# wifiserial.net
KiCad netlist of a schematic drawn in EAGLE
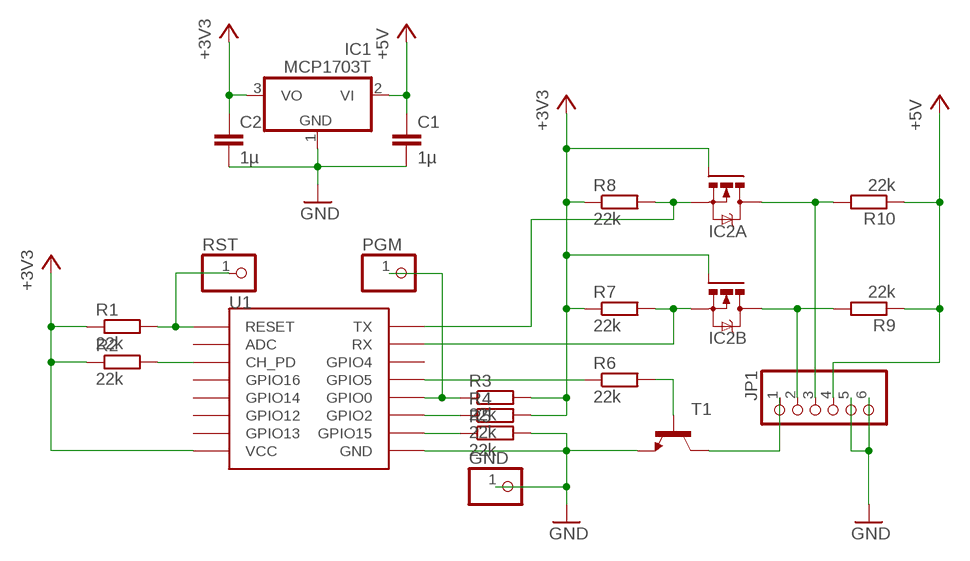
[diagram p0: schematic, sheet 1]

(export (version "E")
  (design (tool "Eeschema 10.0.6"))
  (components
    (comp (ref "C1")
      (value "1µ")
      (footprint "eagle-import:C0805K")
      (libsource (lib "eagle-import") (part "C-EUC0805K"))
    )
    (comp (ref "C2")
      (value "1µ")
      (footprint "eagle-import:C0805K")
      (libsource (lib "eagle-import") (part "C-EUC0805K"))
    )
    (comp (ref "GND")
      (value "PINHD-1X1")
      (footprint "eagle-import:1X01")
      (libsource (lib "eagle-import") (part "PINHD-1X1"))
    )
    (comp (ref "IC1")
      (value "MCP1703T")
      (footprint "eagle-import:SOT-89")
      (libsource (lib "eagle-import") (part "VREG-SOT89"))
    )
    (comp (ref "IC2")
      (value "NFET2-SSOT6")
      (footprint "eagle-import:SSOT-6")
      (libsource (lib "eagle-import") (part "NFET2-SSOT6"))
    )
    (comp (ref "JP1")
      (value "PINHD-1X6")
      (footprint "eagle-import:1X06")
      (libsource (lib "eagle-import") (part "PINHD-1X6"))
    )
    (comp (ref "PGM")
      (value "PINHD-1X1")
      (footprint "eagle-import:1X01")
      (libsource (lib "eagle-import") (part "PINHD-1X1"))
    )
    (comp (ref "R1")
      (value "22k")
      (footprint "eagle-import:R0805")
      (libsource (lib "eagle-import") (part "R-EU_R0805"))
    )
    (comp (ref "R2")
      (value "22k")
      (footprint "eagle-import:R0805")
      (libsource (lib "eagle-import") (part "R-EU_R0805"))
    )
    (comp (ref "R3")
      (value "22k")
      (footprint "eagle-import:R0805")
      (libsource (lib "eagle-import") (part "R-EU_R0805"))
    )
    (comp (ref "R4")
      (value "22k")
      (footprint "eagle-import:R0805")
      (libsource (lib "eagle-import") (part "R-EU_R0805"))
    )
    (comp (ref "R5")
      (value "22k")
      (footprint "eagle-import:R0805")
      (libsource (lib "eagle-import") (part "R-EU_R0805"))
    )
    (comp (ref "R6")
      (value "22k")
      (footprint "eagle-import:R0805")
      (libsource (lib "eagle-import") (part "R-EU_R0805"))
    )
    (comp (ref "R7")
      (value "22k")
      (footprint "eagle-import:R0805")
      (libsource (lib "eagle-import") (part "R-EU_R0805"))
    )
    (comp (ref "R8")
      (value "22k")
      (footprint "eagle-import:R0805")
      (libsource (lib "eagle-import") (part "R-EU_R0805"))
    )
    (comp (ref "R9")
      (value "22k")
      (footprint "eagle-import:R0805")
      (libsource (lib "eagle-import") (part "R-EU_R0805"))
    )
    (comp (ref "R10")
      (value "22k")
      (footprint "eagle-import:R0805")
      (libsource (lib "eagle-import") (part "R-EU_R0805"))
    )
    (comp (ref "RST")
      (value "PINHD-1X1")
      (footprint "eagle-import:1X01")
      (libsource (lib "eagle-import") (part "PINHD-1X1"))
    )
    (comp (ref "T1")
      (value "-NPN-SOT23-EBC")
      (footprint "eagle-import:SOT23-EBC")
      (libsource (lib "eagle-import") (part "-NPN-SOT23-EBC"))
    )
    (comp (ref "U1")
      (value "ESP12SMD")
      (footprint "eagle-import:ESP12-SMD")
      (libsource (lib "eagle-import") (part "ESP12SMD"))
    )
  )
  (nets
    (net (code "1") (name "+3V3") (class "Default")
      (node (ref "C2") (pin "1") (pinfunction "1_1") (pintype "passive"))
      (node (ref "IC1") (pin "3") (pinfunction "VO_3") (pintype "passive"))
      (node (ref "IC2") (pin "1") (pinfunction "G_1") (pintype "passive"))
      (node (ref "IC2") (pin "3") (pinfunction "G_3") (pintype "passive"))
      (node (ref "R1") (pin "1") (pinfunction "1_1") (pintype "passive"))
      (node (ref "R2") (pin "1") (pinfunction "1_1") (pintype "passive"))
      (node (ref "R3") (pin "2") (pinfunction "2_2") (pintype "passive"))
      (node (ref "R4") (pin "2") (pinfunction "2_2") (pintype "passive"))
      (node (ref "R7") (pin "1") (pinfunction "1_1") (pintype "passive"))
      (node (ref "R8") (pin "1") (pinfunction "1_1") (pintype "passive"))
      (node (ref "U1") (pin "VCC") (pinfunction "VCC_VCC") (pintype "bidirectional"))
    )
    (net (code "2") (name "+5V") (class "Default")
      (node (ref "C1") (pin "1") (pinfunction "1_1") (pintype "passive"))
      (node (ref "IC1") (pin "2") (pinfunction "VI_2") (pintype "input"))
      (node (ref "JP1") (pin "4") (pinfunction "4_4") (pintype "passive"))
      (node (ref "R10") (pin "1") (pinfunction "1_1") (pintype "passive"))
      (node (ref "R9") (pin "1") (pinfunction "1_1") (pintype "passive"))
    )
    (net (code "3") (name "GND") (class "Default")
      (node (ref "C1") (pin "2") (pinfunction "2_2") (pintype "passive"))
      (node (ref "C2") (pin "2") (pinfunction "2_2") (pintype "passive"))
      (node (ref "GND") (pin "1") (pinfunction "1_1") (pintype "passive"))
      (node (ref "IC1") (pin "1") (pinfunction "GND_1") (pintype "passive"))
      (node (ref "JP1") (pin "5") (pinfunction "5_5") (pintype "passive"))
      (node (ref "JP1") (pin "6") (pinfunction "6_6") (pintype "passive"))
      (node (ref "R5") (pin "2") (pinfunction "2_2") (pintype "passive"))
      (node (ref "T1") (pin "E") (pinfunction "E_E") (pintype "passive"))
      (node (ref "U1") (pin "GND") (pinfunction "GND_GND") (pintype "bidirectional"))
    )
    (net (code "4") (name "Net-(IC2A-D)") (class "Default")
      (node (ref "IC2") (pin "6") (pinfunction "D_6") (pintype "passive"))
      (node (ref "JP1") (pin "3") (pinfunction "3_3") (pintype "passive"))
      (node (ref "R10") (pin "2") (pinfunction "2_2") (pintype "passive"))
    )
    (net (code "5") (name "Net-(IC2A-S)") (class "Default")
      (node (ref "IC2") (pin "5") (pinfunction "S_5") (pintype "passive"))
      (node (ref "R8") (pin "2") (pinfunction "2_2") (pintype "passive"))
      (node (ref "U1") (pin "TXD0") (pinfunction "TX_TXD0") (pintype "bidirectional"))
    )
    (net (code "6") (name "Net-(IC2B-D)") (class "Default")
      (node (ref "IC2") (pin "4") (pinfunction "D_4") (pintype "passive"))
      (node (ref "JP1") (pin "2") (pinfunction "2_2") (pintype "passive"))
      (node (ref "R9") (pin "2") (pinfunction "2_2") (pintype "passive"))
    )
    (net (code "7") (name "Net-(IC2B-S)") (class "Default")
      (node (ref "IC2") (pin "2") (pinfunction "S_2") (pintype "passive"))
      (node (ref "R7") (pin "2") (pinfunction "2_2") (pintype "passive"))
      (node (ref "U1") (pin "RXD0") (pinfunction "RX_RXD0") (pintype "bidirectional"))
    )
    (net (code "8") (name "Net-(JP1-Pad1)") (class "Default")
      (node (ref "JP1") (pin "1") (pinfunction "1_1") (pintype "passive"))
      (node (ref "T1") (pin "C") (pinfunction "C_C") (pintype "passive"))
    )
    (net (code "9") (name "Net-(PGM-Pad1)") (class "Default")
      (node (ref "PGM") (pin "1") (pinfunction "1_1") (pintype "passive"))
      (node (ref "R3") (pin "1") (pinfunction "1_1") (pintype "passive"))
      (node (ref "U1") (pin "GPIO0") (pinfunction "GPIO0_GPIO0") (pintype "bidirectional"))
    )
    (net (code "10") (name "Net-(R1-Pad2)") (class "Default")
      (node (ref "R1") (pin "2") (pinfunction "2_2") (pintype "passive"))
      (node (ref "RST") (pin "1") (pinfunction "1_1") (pintype "passive"))
      (node (ref "U1") (pin "RESET") (pinfunction "RESET_RESET") (pintype "bidirectional"))
    )
    (net (code "11") (name "Net-(R2-Pad2)") (class "Default")
      (node (ref "R2") (pin "2") (pinfunction "2_2") (pintype "passive"))
      (node (ref "U1") (pin "CH_PD") (pinfunction "CH_PD_CH_PD") (pintype "bidirectional"))
    )
    (net (code "12") (name "Net-(R4-Pad1)") (class "Default")
      (node (ref "R4") (pin "1") (pinfunction "1_1") (pintype "passive"))
      (node (ref "U1") (pin "GPIO2") (pinfunction "GPIO2_GPIO2") (pintype "bidirectional"))
    )
    (net (code "13") (name "Net-(R5-Pad1)") (class "Default")
      (node (ref "R5") (pin "1") (pinfunction "1_1") (pintype "passive"))
      (node (ref "U1") (pin "GPIO15") (pinfunction "GPIO15_GPIO15") (pintype "bidirectional"))
    )
    (net (code "14") (name "Net-(R6-Pad1)") (class "Default")
      (node (ref "R6") (pin "1") (pinfunction "1_1") (pintype "passive"))
      (node (ref "U1") (pin "GPIO5") (pinfunction "GPIO5_GPIO5") (pintype "bidirectional"))
    )
    (net (code "15") (name "Net-(R6-Pad2)") (class "Default")
      (node (ref "R6") (pin "2") (pinfunction "2_2") (pintype "passive"))
      (node (ref "T1") (pin "B") (pinfunction "B_B") (pintype "passive"))
    )
    (net (code "16") (name "unconnected-(U1-PadADC)") (class "Default")
      (node (ref "U1") (pin "ADC") (pinfunction "ADC_ADC") (pintype "bidirectional"))
    )
    (net (code "17") (name "unconnected-(U1-PadGPIO4)") (class "Default")
      (node (ref "U1") (pin "GPIO4") (pinfunction "GPIO4_GPIO4") (pintype "bidirectional"))
    )
    (net (code "18") (name "unconnected-(U1-PadGPIO12)") (class "Default")
      (node (ref "U1") (pin "GPIO12") (pinfunction "GPIO12_GPIO12") (pintype "bidirectional"))
    )
    (net (code "19") (name "unconnected-(U1-PadGPIO13)") (class "Default")
      (node (ref "U1") (pin "GPIO13") (pinfunction "GPIO13_GPIO13") (pintype "bidirectional"))
    )
    (net (code "20") (name "unconnected-(U1-PadGPIO14)") (class "Default")
      (node (ref "U1") (pin "GPIO14") (pinfunction "GPIO14_GPIO14") (pintype "bidirectional"))
    )
    (net (code "21") (name "unconnected-(U1-PadGPIO16)") (class "Default")
      (node (ref "U1") (pin "GPIO16") (pinfunction "GPIO16_GPIO16") (pintype "bidirectional"))
    )
  )
)
